# microsd.net
KiCad netlist of a schematic drawn in Altium Designer
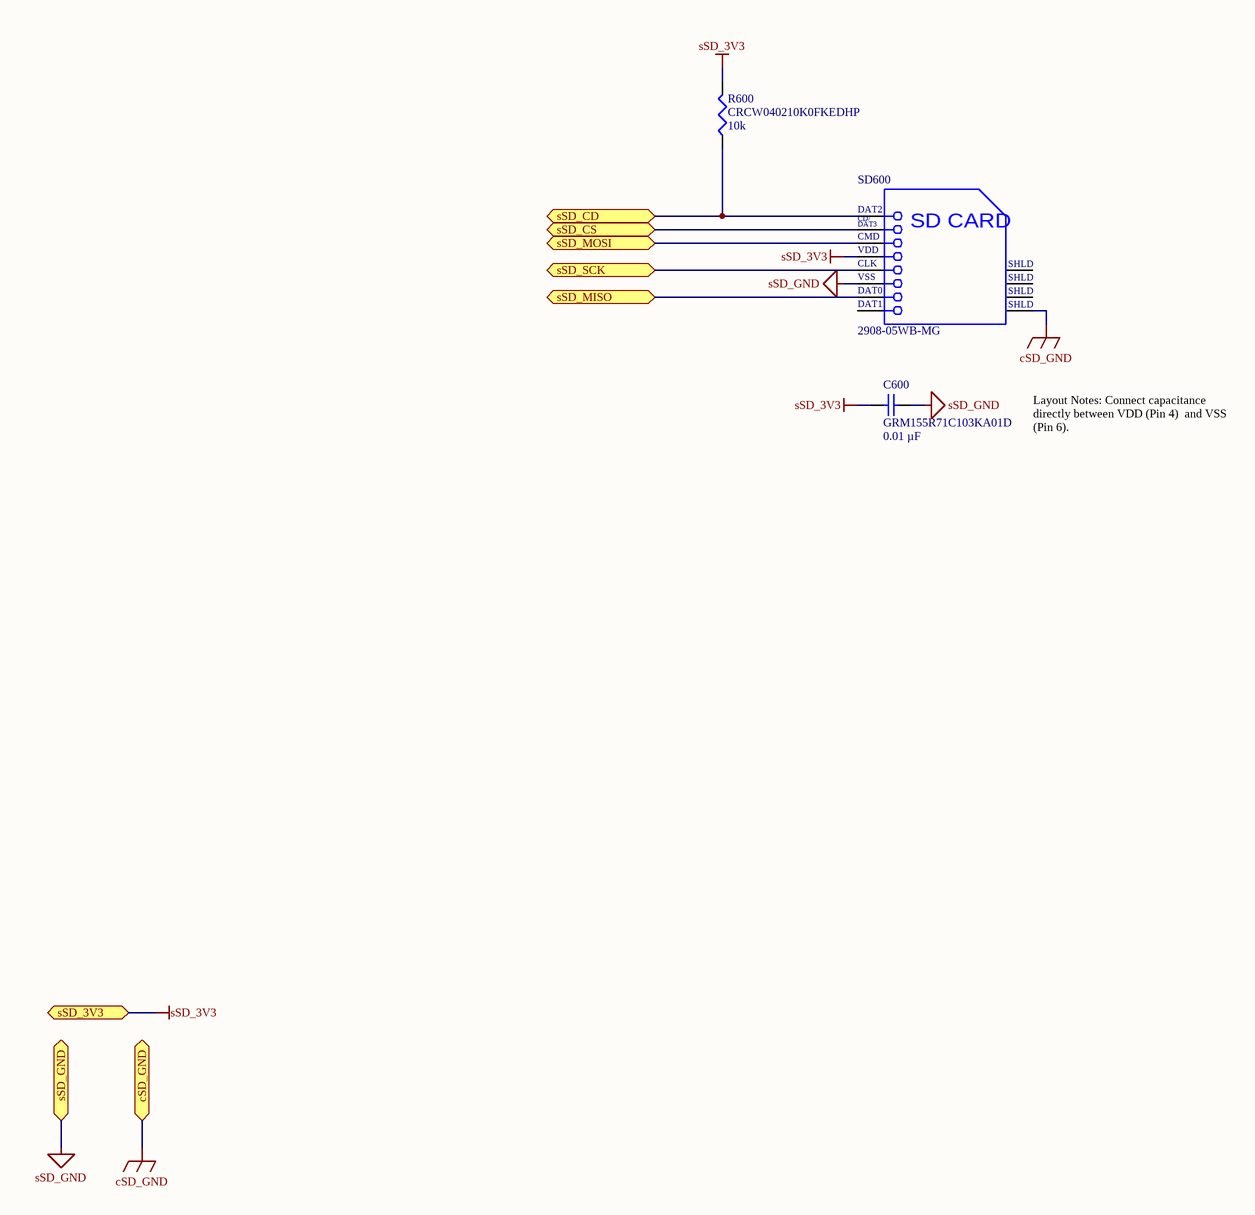
[diagram p0: _microsd.SchDoc]

(export (version "E")
  (design (tool "Eeschema 10.0.6"))
  (components
    (comp (ref "C600")
      (value "GRM155R71C103KA01D")
      (footprint "0402")
      (description "Cap, 0.01 µF, 16 V, X7R")
      (fields (field (name "ALTIUM_VALUE") "0.01 µF") (field (name "PUBLISHER") "Altium Limited"))
      (libsource (lib "miscellaneous_devices") (part "Cap"))
    )
    (comp (ref "R600")
      (value "CRCW040210K0FKEDHP")
      (footprint "0402")
      (description "0.125W, -55-155C, 1005, 50V, ±1%")
      (fields (field (name "ALTIUM_VALUE") "10k"))
      (libsource (lib "standard_resistors") (part "CRCW0402xxxxFKED"))
    )
    (comp (ref "SD600")
      (value "2908-05WB-MG")
      (footprint "3M-2908-05WB-MG_V")
      (description "Card Connector Micro-SD, 500 VAC, 100 mOhm Min, 0.5 A, RoHS, Tape and Reel")
      (fields (field (name "MANUFACTURER") "3M"))
      (libsource (lib "Altium Content Vault") (part "CN-SD-8-4S"))
    )
  )
  (nets
    (net (code "1") (name "/sSD_CD") (class "Default")
      (node (ref "R600") (pin "1") (pinfunction "1_1") (pintype "passive"))
      (node (ref "SD600") (pin "1") (pinfunction "DAT2_1") (pintype "passive"))
    )
    (net (code "2") (name "/sSD_CS") (class "Default")
      (node (ref "SD600") (pin "2") (pinfunction "CD/DAT3_2") (pintype "passive"))
    )
    (net (code "3") (name "/sSD_MISO") (class "Default")
      (node (ref "SD600") (pin "7") (pinfunction "DAT0_7") (pintype "passive"))
    )
    (net (code "4") (name "/sSD_MOSI") (class "Default")
      (node (ref "SD600") (pin "3") (pinfunction "CMD_3") (pintype "passive"))
    )
    (net (code "5") (name "/sSD_SCK") (class "Default")
      (node (ref "SD600") (pin "5") (pinfunction "CLK_5") (pintype "passive"))
    )
    (net (code "6") (name "cSD_GND") (class "Default")
      (node (ref "SD600") (pin "12") (pinfunction "SHLD_12") (pintype "passive"))
    )
    (net (code "7") (name "sSD_3V3") (class "Default")
      (node (ref "C600") (pin "2") (pinfunction "2_2") (pintype "passive"))
      (node (ref "R600") (pin "2") (pinfunction "2_2") (pintype "passive"))
      (node (ref "SD600") (pin "4") (pinfunction "VDD_4") (pintype "passive"))
    )
    (net (code "8") (name "sSD_GND") (class "Default")
      (node (ref "C600") (pin "1") (pinfunction "1_1") (pintype "passive"))
      (node (ref "SD600") (pin "6") (pinfunction "VSS_6") (pintype "passive"))
    )
    (net (code "9") (name "unconnected-(SD600-DAT1-Pad8)") (class "Default")
      (node (ref "SD600") (pin "8") (pinfunction "DAT1_8") (pintype "passive"))
    )
    (net (code "10") (name "unconnected-(SD600-SHLD-Pad9)") (class "Default")
      (node (ref "SD600") (pin "9") (pinfunction "SHLD_9") (pintype "passive"))
    )
    (net (code "11") (name "unconnected-(SD600-SHLD-Pad10)") (class "Default")
      (node (ref "SD600") (pin "10") (pinfunction "SHLD_10") (pintype "passive"))
    )
    (net (code "12") (name "unconnected-(SD600-SHLD-Pad11)") (class "Default")
      (node (ref "SD600") (pin "11") (pinfunction "SHLD_11") (pintype "passive"))
    )
  )
)
